# motor.net
KiCad netlist of a schematic drawn in Altium Designer
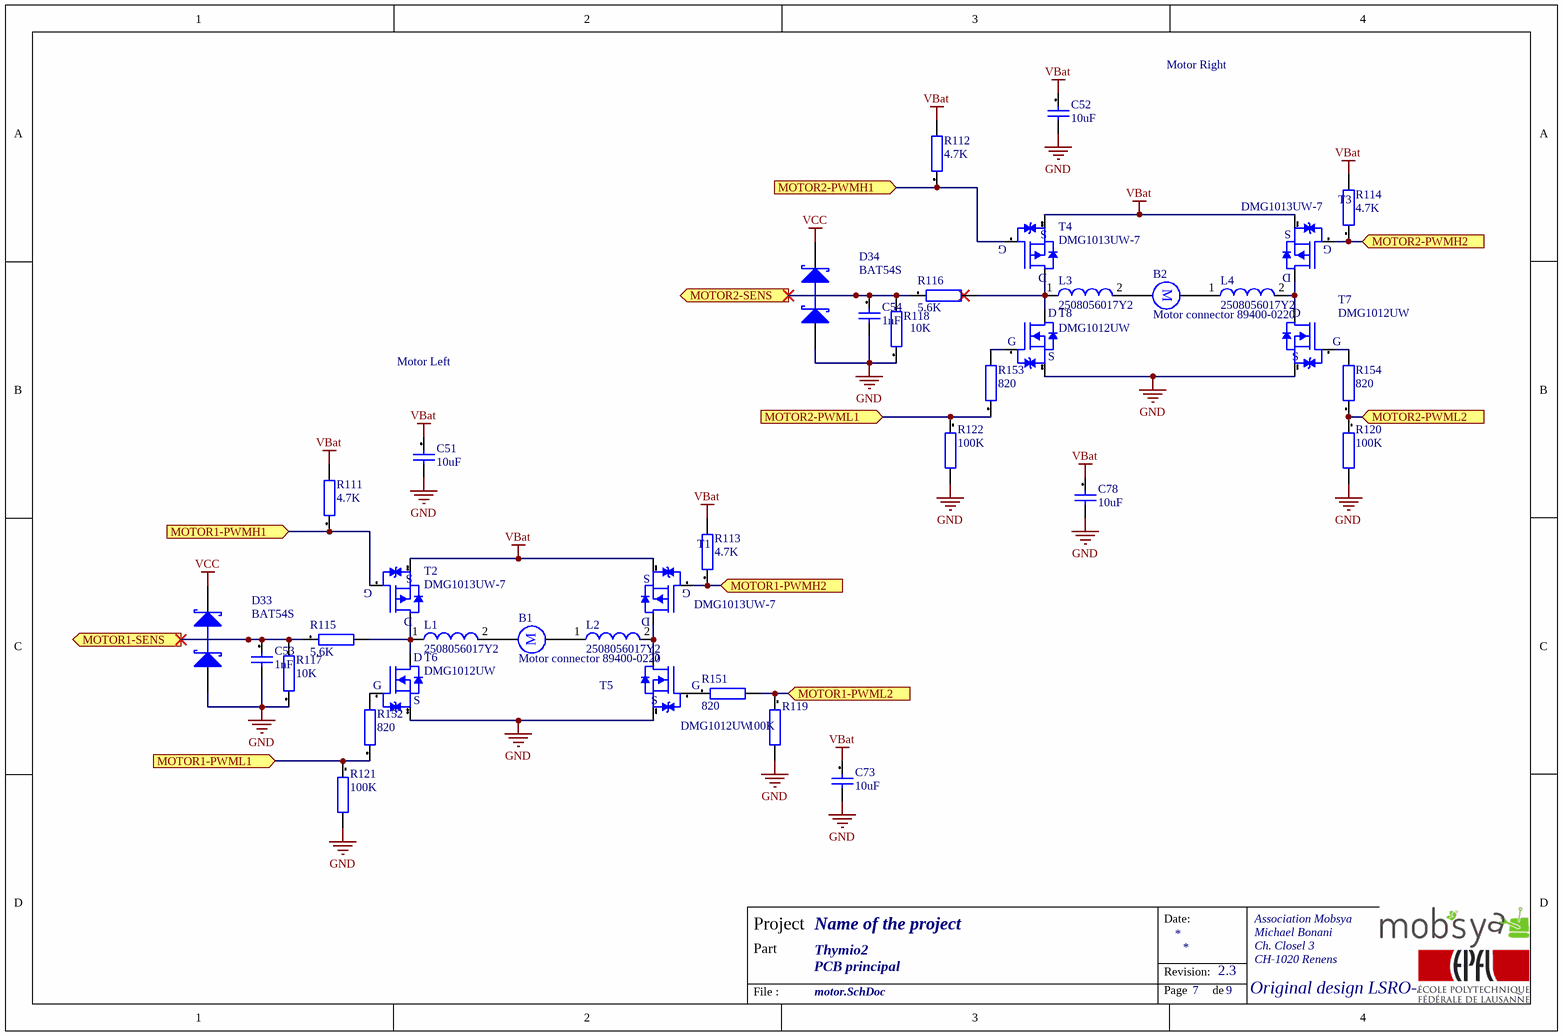
[diagram p0: motor.SchDoc]

(export (version "E")
  (design (tool "Eeschema 10.0.6"))
  (components
    (comp (ref "B1")
      (value "Motor connector 89400-0220")
      (footprint "BAT-2")
      (description "Motor, General Kind")
      (fields (field (name "PUBLISHER") "Altium Limited"))
      (libsource (lib "Miscellaneous Devices") (part "Motor"))
    )
    (comp (ref "B2")
      (value "Motor connector 89400-0220")
      (footprint "BAT-2")
      (description "Motor, General Kind")
      (fields (field (name "PUBLISHER") "Altium Limited"))
      (libsource (lib "Miscellaneous Devices") (part "Motor"))
    )
    (comp (ref "C51")
      (value "10uF")
      (footprint "CAPC1005X05N")
      (description "Capacitor")
      (fields (field (name "MANUFACTURER") "Taiyo Yuden") (field (name "VOLTAGE") "6.3"))
      (libsource (lib "LSRO1Altium") (part "CAP-NP"))
    )
    (comp (ref "C52")
      (value "10uF")
      (footprint "CAPC1005X05N")
      (description "Capacitor")
      (fields (field (name "MANUFACTURER") "Taiyo Yuden") (field (name "VOLTAGE") "6.3"))
      (libsource (lib "LSRO1Altium") (part "CAP-NP"))
    )
    (comp (ref "C53")
      (value "1nF")
      (footprint "CAPC1005X05N")
      (description "Capacitor")
      (fields (field (name "MANUFACTURER") "Kemet") (field (name "VOLTAGE") "50"))
      (libsource (lib "LSRO1Altium") (part "CAP-NP"))
    )
    (comp (ref "C54")
      (value "1nF")
      (footprint "CAPC1005X05N")
      (description "Capacitor")
      (fields (field (name "MANUFACTURER") "Kemet") (field (name "VOLTAGE") "50"))
      (libsource (lib "LSRO1Altium") (part "CAP-NP"))
    )
    (comp (ref "C73")
      (value "10uF")
      (footprint "CAPC1005X05N")
      (description "Capacitor")
      (fields (field (name "MANUFACTURER") "Taiyo Yuden") (field (name "VOLTAGE") "6.3"))
      (libsource (lib "LSRO1Altium") (part "CAP-NP"))
    )
    (comp (ref "C78")
      (value "10uF")
      (footprint "CAPC1005X05N")
      (description "Capacitor")
      (fields (field (name "MANUFACTURER") "Taiyo Yuden") (field (name "VOLTAGE") "6.3"))
      (libsource (lib "LSRO1Altium") (part "CAP-NP"))
    )
    (comp (ref "D33")
      (value "BAT54S")
      (footprint "SOT23_N")
      (description "Schottky Barrier Double Diode")
      (fields (field (name "PUBLISHER") "Altium Limited"))
      (libsource (lib "Philips Discrete Diode - Schottky") (part "BAT54S"))
    )
    (comp (ref "D34")
      (value "BAT54S")
      (footprint "SOT23_N")
      (description "Schottky Barrier Double Diode")
      (fields (field (name "PUBLISHER") "Altium Limited"))
      (libsource (lib "Philips Discrete Diode - Schottky") (part "BAT54S"))
    )
    (comp (ref "L1")
      (value "2508056017Y2")
      (footprint "INDC2012X11L")
      (description "SMD EMI Suppression Ferrite Bead WE-CBF, Z = 600 Ohm")
      (libsource (lib "WE-CBF SMD EMI Suppression Ferrite Bead") (part "74279204"))
    )
    (comp (ref "L2")
      (value "2508056017Y2")
      (footprint "INDC2012X11L")
      (description "SMD EMI Suppression Ferrite Bead WE-CBF, Z = 600 Ohm")
      (libsource (lib "WE-CBF SMD EMI Suppression Ferrite Bead") (part "74279204"))
    )
    (comp (ref "L3")
      (value "2508056017Y2")
      (footprint "INDC2012X11L")
      (description "SMD EMI Suppression Ferrite Bead WE-CBF, Z = 600 Ohm")
      (libsource (lib "WE-CBF SMD EMI Suppression Ferrite Bead") (part "74279204"))
    )
    (comp (ref "L4")
      (value "2508056017Y2")
      (footprint "INDC2012X11L")
      (description "SMD EMI Suppression Ferrite Bead WE-CBF, Z = 600 Ohm")
      (libsource (lib "WE-CBF SMD EMI Suppression Ferrite Bead") (part "74279204"))
    )
    (comp (ref "R111")
      (value "4.7K")
      (footprint "RESC1005X04N")
      (description "Resistor")
      (fields (field (name "TOLERANCE") "+/-1") (field (name "MANUFACTURER") "Vishay"))
      (libsource (lib "LSRO1Altium") (part "RES"))
    )
    (comp (ref "R112")
      (value "4.7K")
      (footprint "RESC1005X04N")
      (description "Resistor")
      (fields (field (name "TOLERANCE") "+/-1") (field (name "MANUFACTURER") "Vishay"))
      (libsource (lib "LSRO1Altium") (part "RES"))
    )
    (comp (ref "R113")
      (value "4.7K")
      (footprint "RESC1005X04N")
      (description "Resistor")
      (fields (field (name "TOLERANCE") "+/-1") (field (name "MANUFACTURER") "Vishay"))
      (libsource (lib "LSRO1Altium") (part "RES"))
    )
    (comp (ref "R114")
      (value "4.7K")
      (footprint "RESC1005X04N")
      (description "Resistor")
      (fields (field (name "TOLERANCE") "+/-1") (field (name "MANUFACTURER") "Vishay"))
      (libsource (lib "LSRO1Altium") (part "RES"))
    )
    (comp (ref "R115")
      (value "5.6K")
      (footprint "RESC1005X04N")
      (description "Resistor")
      (fields (field (name "TOLERANCE") "+/-1") (field (name "MANUFACTURER") "Vishay"))
      (libsource (lib "LSRO1Altium") (part "RES"))
    )
    (comp (ref "R116")
      (value "5.6K")
      (footprint "RESC1005X04N")
      (description "Resistor")
      (fields (field (name "TOLERANCE") "+/-1") (field (name "MANUFACTURER") "Vishay"))
      (libsource (lib "LSRO1Altium") (part "RES"))
    )
    (comp (ref "R117")
      (value "10K")
      (footprint "RESC1005X04N")
      (description "Resistor")
      (fields (field (name "TOLERANCE") "+/-1%") (field (name "MANUFACTURER") "Multicomp"))
      (libsource (lib "LSRO1Altium") (part "RES"))
    )
    (comp (ref "R118")
      (value "10K")
      (footprint "RESC1005X04N")
      (description "Resistor")
      (fields (field (name "TOLERANCE") "+/-1%") (field (name "MANUFACTURER") "Multicomp"))
      (libsource (lib "LSRO1Altium") (part "RES"))
    )
    (comp (ref "R119")
      (value "100K")
      (footprint "RESC1005X04N")
      (description "Resistor")
      (fields (field (name "TOLERANCE") "+/-1") (field (name "MANUFACTURER") "Vishay"))
      (libsource (lib "LSRO1Altium") (part "RES"))
    )
    (comp (ref "R120")
      (value "100K")
      (footprint "RESC1005X04N")
      (description "Resistor")
      (fields (field (name "TOLERANCE") "+/-1") (field (name "MANUFACTURER") "Vishay"))
      (libsource (lib "LSRO1Altium") (part "RES"))
    )
    (comp (ref "R121")
      (value "100K")
      (footprint "RESC1005X04N")
      (description "Resistor")
      (fields (field (name "TOLERANCE") "+/-1") (field (name "MANUFACTURER") "Vishay"))
      (libsource (lib "LSRO1Altium") (part "RES"))
    )
    (comp (ref "R122")
      (value "100K")
      (footprint "RESC1005X04N")
      (description "Resistor")
      (fields (field (name "TOLERANCE") "+/-1") (field (name "MANUFACTURER") "Vishay"))
      (libsource (lib "LSRO1Altium") (part "RES"))
    )
    (comp (ref "R151")
      (value "820")
      (footprint "RESC1005X04N")
      (description "Resistor")
      (fields (field (name "TOLERANCE") "+/-1") (field (name "MANUFACTURER") "Vishay"))
      (libsource (lib "LSRO1Altium") (part "RES"))
    )
    (comp (ref "R152")
      (value "820")
      (footprint "RESC1005X04N")
      (description "Resistor")
      (fields (field (name "TOLERANCE") "+/-1") (field (name "MANUFACTURER") "Vishay"))
      (libsource (lib "LSRO1Altium") (part "RES"))
    )
    (comp (ref "R153")
      (value "820")
      (footprint "RESC1005X04N")
      (description "Resistor")
      (fields (field (name "TOLERANCE") "+/-1") (field (name "MANUFACTURER") "Vishay"))
      (libsource (lib "LSRO1Altium") (part "RES"))
    )
    (comp (ref "R154")
      (value "820")
      (footprint "RESC1005X04N")
      (description "Resistor")
      (fields (field (name "TOLERANCE") "+/-1") (field (name "MANUFACTURER") "Vishay"))
      (libsource (lib "LSRO1Altium") (part "RES"))
    )
    (comp (ref "T1")
      (value "DMG1013UW-7")
      (footprint "SOT65P210X100-3N")
      (description "Transistor MOSFET 1 x P Pining : 1=G, 2=S, 3=D")
      (fields (field (name "VERIFIEDBY") "DBR"))
      (libsource (lib "Transistors") (part "DMG1013T"))
    )
    (comp (ref "T2")
      (value "DMG1013UW-7")
      (footprint "SOT65P210X100-3N")
      (description "Transistor MOSFET 1 x P Pining : 1=G, 2=S, 3=D")
      (fields (field (name "VERIFIEDBY") "DBR"))
      (libsource (lib "Transistors") (part "DMG1013T"))
    )
    (comp (ref "T3")
      (value "DMG1013UW-7")
      (footprint "SOT65P210X100-3N")
      (description "Transistor MOSFET 1 x P Pining : 1=G, 2=S, 3=D")
      (fields (field (name "VERIFIEDBY") "DBR"))
      (libsource (lib "Transistors") (part "DMG1013T"))
    )
    (comp (ref "T4")
      (value "DMG1013UW-7")
      (footprint "SOT65P210X100-3N")
      (description "Transistor MOSFET 1 x P Pining : 1=G, 2=S, 3=D")
      (fields (field (name "VERIFIEDBY") "DBR"))
      (libsource (lib "Transistors") (part "DMG1013T"))
    )
    (comp (ref "T5")
      (value "DMG1012UW")
      (footprint "SOT65P210X100-3N")
      (description "Transistor MOSFET 1 x N, Pining : 1=G, 2=S, 3=D")
      (fields (field (name "VERIFIEDBY") "DBR"))
      (libsource (lib "Transistors") (part "DMG1012T"))
    )
    (comp (ref "T6")
      (value "DMG1012UW")
      (footprint "SOT65P210X100-3N")
      (description "Transistor MOSFET 1 x N, Pining : 1=G, 2=S, 3=D")
      (fields (field (name "VERIFIEDBY") "DBR"))
      (libsource (lib "Transistors") (part "DMG1012T"))
    )
    (comp (ref "T7")
      (value "DMG1012UW")
      (footprint "SOT65P210X100-3N")
      (description "Transistor MOSFET 1 x N, Pining : 1=G, 2=S, 3=D")
      (fields (field (name "VERIFIEDBY") "DBR"))
      (libsource (lib "Transistors") (part "DMG1012T"))
    )
    (comp (ref "T8")
      (value "DMG1012UW")
      (footprint "SOT65P210X100-3N")
      (description "Transistor MOSFET 1 x N, Pining : 1=G, 2=S, 3=D")
      (fields (field (name "VERIFIEDBY") "DBR"))
      (libsource (lib "Transistors") (part "DMG1012T"))
    )
  )
  (nets
    (net (code "1") (name "/MOTOR1-PWMH1") (class "Default")
      (node (ref "R111") (pin "1") (pinfunction "1_1") (pintype "passive"))
      (node (ref "T2") (pin "1") (pinfunction "G_1") (pintype "passive"))
    )
    (net (code "2") (name "/MOTOR1-PWMH2") (class "Default")
      (node (ref "R113") (pin "1") (pinfunction "1_1") (pintype "passive"))
      (node (ref "T1") (pin "1") (pinfunction "G_1") (pintype "passive"))
    )
    (net (code "3") (name "/MOTOR1-PWML1") (class "Default")
      (node (ref "R121") (pin "1") (pinfunction "1_1") (pintype "passive"))
      (node (ref "R152") (pin "1") (pinfunction "1_1") (pintype "passive"))
    )
    (net (code "4") (name "/MOTOR1-PWML2") (class "Default")
      (node (ref "R119") (pin "1") (pinfunction "1_1") (pintype "passive"))
      (node (ref "R151") (pin "2") (pinfunction "2_2") (pintype "passive"))
    )
    (net (code "5") (name "/MOTOR1-SENS") (class "Default")
      (node (ref "C53") (pin "1") (pinfunction "1_1") (pintype "passive"))
      (node (ref "D33") (pin "3") (pinfunction "C_3") (pintype "passive"))
      (node (ref "R115") (pin "1") (pinfunction "1_1") (pintype "passive"))
      (node (ref "R117") (pin "2") (pinfunction "2_2") (pintype "passive"))
    )
    (net (code "6") (name "/MOTOR2-PWMH1") (class "Default")
      (node (ref "R112") (pin "1") (pinfunction "1_1") (pintype "passive"))
      (node (ref "T4") (pin "1") (pinfunction "G_1") (pintype "passive"))
    )
    (net (code "7") (name "/MOTOR2-PWMH2") (class "Default")
      (node (ref "R114") (pin "1") (pinfunction "1_1") (pintype "passive"))
      (node (ref "T3") (pin "1") (pinfunction "G_1") (pintype "passive"))
    )
    (net (code "8") (name "/MOTOR2-PWML1") (class "Default")
      (node (ref "R122") (pin "1") (pinfunction "1_1") (pintype "passive"))
      (node (ref "R153") (pin "1") (pinfunction "1_1") (pintype "passive"))
    )
    (net (code "9") (name "/MOTOR2-PWML2") (class "Default")
      (node (ref "R120") (pin "1") (pinfunction "1_1") (pintype "passive"))
      (node (ref "R154") (pin "1") (pinfunction "1_1") (pintype "passive"))
    )
    (net (code "10") (name "/MOTOR2-SENS") (class "Default")
      (node (ref "C54") (pin "1") (pinfunction "1_1") (pintype "passive"))
      (node (ref "D34") (pin "3") (pinfunction "C_3") (pintype "passive"))
      (node (ref "R116") (pin "1") (pinfunction "1_1") (pintype "passive"))
      (node (ref "R118") (pin "2") (pinfunction "2_2") (pintype "passive"))
    )
    (net (code "11") (name "GND") (class "Default")
      (node (ref "C51") (pin "2") (pinfunction "2_2") (pintype "passive"))
      (node (ref "C52") (pin "2") (pinfunction "2_2") (pintype "passive"))
      (node (ref "C53") (pin "2") (pinfunction "2_2") (pintype "passive"))
      (node (ref "C54") (pin "2") (pinfunction "2_2") (pintype "passive"))
      (node (ref "C73") (pin "2") (pinfunction "2_2") (pintype "passive"))
      (node (ref "C78") (pin "2") (pinfunction "2_2") (pintype "passive"))
      (node (ref "D33") (pin "1") (pinfunction "A_1") (pintype "passive"))
      (node (ref "D34") (pin "1") (pinfunction "A_1") (pintype "passive"))
      (node (ref "R117") (pin "1") (pinfunction "1_1") (pintype "passive"))
      (node (ref "R118") (pin "1") (pinfunction "1_1") (pintype "passive"))
      (node (ref "R119") (pin "2") (pinfunction "2_2") (pintype "passive"))
      (node (ref "R120") (pin "2") (pinfunction "2_2") (pintype "passive"))
      (node (ref "R121") (pin "2") (pinfunction "2_2") (pintype "passive"))
      (node (ref "R122") (pin "2") (pinfunction "2_2") (pintype "passive"))
      (node (ref "T5") (pin "2") (pinfunction "S_2") (pintype "passive"))
      (node (ref "T6") (pin "2") (pinfunction "S_2") (pintype "passive"))
      (node (ref "T7") (pin "2") (pinfunction "S_2") (pintype "passive"))
      (node (ref "T8") (pin "2") (pinfunction "S_2") (pintype "passive"))
    )
    (net (code "12") (name "Net-(B1-Pad1)") (class "Default")
      (node (ref "B1") (pin "1") (pinfunction "1_1") (pintype "passive"))
      (node (ref "L1") (pin "2") (pinfunction "2_2") (pintype "passive"))
    )
    (net (code "13") (name "Net-(B1-Pad2)") (class "Default")
      (node (ref "B1") (pin "2") (pinfunction "2_2") (pintype "passive"))
      (node (ref "L2") (pin "1") (pinfunction "1_1") (pintype "passive"))
    )
    (net (code "14") (name "Net-(B2-Pad1)") (class "Default")
      (node (ref "B2") (pin "1") (pinfunction "1_1") (pintype "passive"))
      (node (ref "L4") (pin "1") (pinfunction "1_1") (pintype "passive"))
    )
    (net (code "15") (name "Net-(B2-Pad2)") (class "Default")
      (node (ref "B2") (pin "2") (pinfunction "2_2") (pintype "passive"))
      (node (ref "L3") (pin "2") (pinfunction "2_2") (pintype "passive"))
    )
    (net (code "16") (name "Net-(T1-D)") (class "Default")
      (node (ref "L2") (pin "2") (pinfunction "2_2") (pintype "passive"))
      (node (ref "T1") (pin "3") (pinfunction "D_3") (pintype "passive"))
      (node (ref "T5") (pin "3") (pinfunction "D_3") (pintype "passive"))
    )
    (net (code "17") (name "Net-(T2-D)") (class "Default")
      (node (ref "L1") (pin "1") (pinfunction "1_1") (pintype "passive"))
      (node (ref "R115") (pin "2") (pinfunction "2_2") (pintype "passive"))
      (node (ref "T2") (pin "3") (pinfunction "D_3") (pintype "passive"))
      (node (ref "T6") (pin "3") (pinfunction "D_3") (pintype "passive"))
    )
    (net (code "18") (name "Net-(T3-D)") (class "Default")
      (node (ref "L4") (pin "2") (pinfunction "2_2") (pintype "passive"))
      (node (ref "T3") (pin "3") (pinfunction "D_3") (pintype "passive"))
      (node (ref "T7") (pin "3") (pinfunction "D_3") (pintype "passive"))
    )
    (net (code "19") (name "Net-(T4-D)") (class "Default")
      (node (ref "L3") (pin "1") (pinfunction "1_1") (pintype "passive"))
      (node (ref "R116") (pin "2") (pinfunction "2_2") (pintype "passive"))
      (node (ref "T4") (pin "3") (pinfunction "D_3") (pintype "passive"))
      (node (ref "T8") (pin "3") (pinfunction "D_3") (pintype "passive"))
    )
    (net (code "20") (name "Net-(T5-G)") (class "Default")
      (node (ref "R151") (pin "1") (pinfunction "1_1") (pintype "passive"))
      (node (ref "T5") (pin "1") (pinfunction "G_1") (pintype "passive"))
    )
    (net (code "21") (name "Net-(T6-G)") (class "Default")
      (node (ref "R152") (pin "2") (pinfunction "2_2") (pintype "passive"))
      (node (ref "T6") (pin "1") (pinfunction "G_1") (pintype "passive"))
    )
    (net (code "22") (name "Net-(T7-G)") (class "Default")
      (node (ref "R154") (pin "2") (pinfunction "2_2") (pintype "passive"))
      (node (ref "T7") (pin "1") (pinfunction "G_1") (pintype "passive"))
    )
    (net (code "23") (name "Net-(T8-G)") (class "Default")
      (node (ref "R153") (pin "2") (pinfunction "2_2") (pintype "passive"))
      (node (ref "T8") (pin "1") (pinfunction "G_1") (pintype "passive"))
    )
    (net (code "24") (name "VBat") (class "Default")
      (node (ref "C51") (pin "1") (pinfunction "1_1") (pintype "passive"))
      (node (ref "C52") (pin "1") (pinfunction "1_1") (pintype "passive"))
      (node (ref "C73") (pin "1") (pinfunction "1_1") (pintype "passive"))
      (node (ref "C78") (pin "1") (pinfunction "1_1") (pintype "passive"))
      (node (ref "R111") (pin "2") (pinfunction "2_2") (pintype "passive"))
      (node (ref "R112") (pin "2") (pinfunction "2_2") (pintype "passive"))
      (node (ref "R113") (pin "2") (pinfunction "2_2") (pintype "passive"))
      (node (ref "R114") (pin "2") (pinfunction "2_2") (pintype "passive"))
      (node (ref "T1") (pin "2") (pinfunction "S_2") (pintype "passive"))
      (node (ref "T2") (pin "2") (pinfunction "S_2") (pintype "passive"))
      (node (ref "T3") (pin "2") (pinfunction "S_2") (pintype "passive"))
      (node (ref "T4") (pin "2") (pinfunction "S_2") (pintype "passive"))
    )
    (net (code "25") (name "VCC") (class "Default")
      (node (ref "D33") (pin "2") (pinfunction "K_2") (pintype "passive"))
      (node (ref "D34") (pin "2") (pinfunction "K_2") (pintype "passive"))
    )
  )
)
